# toplevel_os.net
KiCad netlist of a schematic drawn in Altium Designer
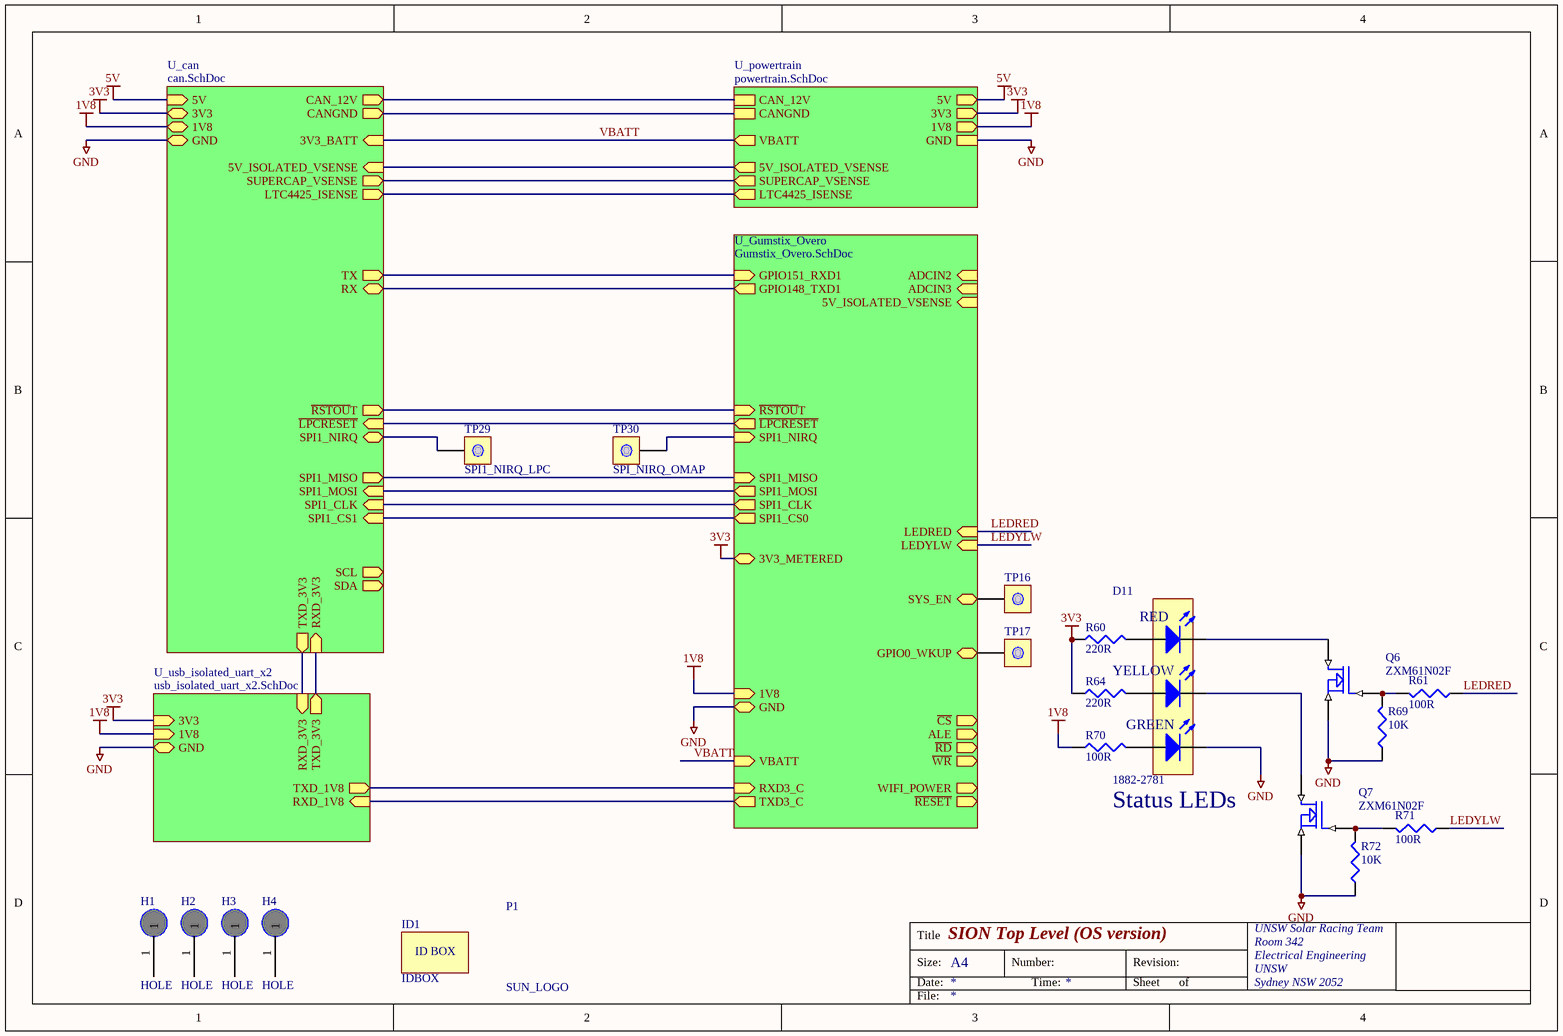
[diagram p0: toplevel_os.SchDoc]

(export (version "E")
  (design (tool "Eeschema 10.0.6"))
  (components
    (comp (ref "D11")
      (value "1882-2781")
      (footprint "LED_TRILEVEL")
      (description "Three level LED")
      (libsource (lib "RCLDQ") (part "LED-TRILEVEL"))
    )
    (comp (ref "H1")
      (value "HOLE")
      (footprint "Connectors:#6")
      (description "Hole")
      (libsource (lib "Miscellaneous") (part "HOLE"))
    )
    (comp (ref "H2")
      (value "HOLE")
      (footprint "Connectors:#6")
      (description "Hole")
      (libsource (lib "Miscellaneous") (part "HOLE"))
    )
    (comp (ref "H3")
      (value "HOLE")
      (footprint "Connectors:#6")
      (description "Hole")
      (libsource (lib "Miscellaneous") (part "HOLE"))
    )
    (comp (ref "H4")
      (value "HOLE")
      (footprint "Connectors:#6")
      (description "Hole")
      (libsource (lib "Miscellaneous") (part "HOLE"))
    )
    (comp (ref "ID1") (value "IDBOX") (footprint "IDBOX") (libsource (lib "Miscellaneous") (part "IDBOX")))
    (comp (ref "P1")
      (value "SUN_LOGO")
      (footprint "SUNSWIFTLOGO")
      (libsource (lib "Miscellaneous") (part "SUN_LOGO"))
    )
    (comp (ref "Q6")
      (value "ZXM61N02F")
      (footprint "SOT23-3")
      (description "1.7A, 20V N-Channel Enhancement mode FET")
      (libsource (lib "RCLDQ") (part "ZXM61N02F"))
    )
    (comp (ref "Q7")
      (value "ZXM61N02F")
      (footprint "SOT23-3")
      (description "1.7A, 20V N-Channel Enhancement mode FET")
      (libsource (lib "RCLDQ") (part "ZXM61N02F"))
    )
    (comp (ref "R60")
      (value "220R")
      (footprint "0603")
      (description "Resistor")
      (libsource (lib "RCLDQ") (part "RES1"))
    )
    (comp (ref "R61")
      (value "100R")
      (footprint "0603")
      (description "Resistor")
      (libsource (lib "RCLDQ") (part "RES1"))
    )
    (comp (ref "R64")
      (value "220R")
      (footprint "0603")
      (description "Resistor")
      (libsource (lib "RCLDQ") (part "RES1"))
    )
    (comp (ref "R69")
      (value "10K")
      (footprint "0603")
      (description "Resistor")
      (libsource (lib "RCLDQ") (part "RES1"))
    )
    (comp (ref "R70")
      (value "100R")
      (footprint "0603")
      (description "Resistor")
      (libsource (lib "RCLDQ") (part "RES1"))
    )
    (comp (ref "R71")
      (value "100R")
      (footprint "0603")
      (description "Resistor")
      (libsource (lib "RCLDQ") (part "RES1"))
    )
    (comp (ref "R72")
      (value "10K")
      (footprint "0603")
      (description "Resistor")
      (libsource (lib "RCLDQ") (part "RES1"))
    )
    (comp (ref "TP16")
      (value "SYS_EN")
      (footprint "TESTPOINT")
      (description "TEST POINT")
      (libsource (lib "") (part "TEST_1"))
    )
    (comp (ref "TP17")
      (value "WKUP")
      (footprint "TESTPOINT")
      (description "TEST POINT")
      (libsource (lib "") (part "TEST_1"))
    )
    (comp (ref "TP29")
      (value "SPI1_NIRQ_LPC")
      (footprint "TESTPOINT")
      (description "TEST POINT")
      (libsource (lib "") (part "TEST_1"))
    )
    (comp (ref "TP30")
      (value "SPI_NIRQ_OMAP")
      (footprint "TESTPOINT")
      (description "TEST POINT")
      (libsource (lib "Miscellaneous") (part "TEST"))
    )
  )
  (nets
    (net (code "8") (name "/GPIO0_WKUP") (class "Default")
      (node (ref "TP17") (pin "0") (pinfunction "TP_0") (pintype "passive"))
    )
    (net (code "10") (name "/LEDRED") (class "Default")
      (node (ref "R61") (pin "1") (pinfunction "1_1") (pintype "passive"))
    )
    (net (code "11") (name "/LEDYLW") (class "Default")
      (node (ref "R71") (pin "1") (pinfunction "1_1") (pintype "passive"))
    )
    (net (code "19") (name "/SPI1_NIRQ") (class "Default")
      (node (ref "TP30") (pin "0") (pinfunction "TP_0") (pintype "passive"))
    )
    (net (code "20") (name "/SPI1_NIRQ_1") (class "Default")
      (node (ref "TP29") (pin "0") (pinfunction "TP_0") (pintype "passive"))
    )
    (net (code "22") (name "/SYS_EN") (class "Default")
      (node (ref "TP16") (pin "0") (pinfunction "TP_0") (pintype "passive"))
    )
    (net (code "36") (name "1V8") (class "Default")
      (node (ref "R70") (pin "1") (pinfunction "1_1") (pintype "passive"))
    )
    (net (code "37") (name "3V3") (class "Default")
      (node (ref "R60") (pin "1") (pinfunction "1_1") (pintype "passive"))
      (node (ref "R64") (pin "1") (pinfunction "1_1") (pintype "passive"))
    )
    (net (code "39") (name "GND") (class "Default")
      (node (ref "D11") (pin "1") (pinfunction "K_1") (pintype "passive"))
      (node (ref "Q6") (pin "2") (pinfunction "S_2") (pintype "input"))
      (node (ref "Q7") (pin "2") (pinfunction "S_2") (pintype "input"))
      (node (ref "R69") (pin "1") (pinfunction "1_1") (pintype "passive"))
      (node (ref "R72") (pin "1") (pinfunction "1_1") (pintype "passive"))
    )
    (net (code "40") (name "Net-(D11-A-Pad4)") (class "Default")
      (node (ref "D11") (pin "4") (pinfunction "A_4") (pintype "passive"))
      (node (ref "R60") (pin "2") (pinfunction "2_2") (pintype "passive"))
    )
    (net (code "41") (name "Net-(D11-A-Pad5)") (class "Default")
      (node (ref "D11") (pin "5") (pinfunction "A_5") (pintype "passive"))
      (node (ref "R64") (pin "2") (pinfunction "2_2") (pintype "passive"))
    )
    (net (code "42") (name "Net-(D11-A-Pad6)") (class "Default")
      (node (ref "D11") (pin "6") (pinfunction "A_6") (pintype "passive"))
      (node (ref "R70") (pin "2") (pinfunction "2_2") (pintype "passive"))
    )
    (net (code "43") (name "Net-(Q6-D)") (class "Default")
      (node (ref "D11") (pin "3") (pinfunction "K_3") (pintype "passive"))
      (node (ref "Q6") (pin "3") (pinfunction "D_3") (pintype "input"))
    )
    (net (code "44") (name "Net-(Q6-G)") (class "Default")
      (node (ref "Q6") (pin "1") (pinfunction "G_1") (pintype "input"))
      (node (ref "R61") (pin "2") (pinfunction "2_2") (pintype "passive"))
      (node (ref "R69") (pin "2") (pinfunction "2_2") (pintype "passive"))
    )
    (net (code "45") (name "Net-(Q7-D)") (class "Default")
      (node (ref "D11") (pin "2") (pinfunction "K_2") (pintype "passive"))
      (node (ref "Q7") (pin "3") (pinfunction "D_3") (pintype "input"))
    )
    (net (code "46") (name "Net-(Q7-G)") (class "Default")
      (node (ref "Q7") (pin "1") (pinfunction "G_1") (pintype "input"))
      (node (ref "R71") (pin "2") (pinfunction "2_2") (pintype "passive"))
      (node (ref "R72") (pin "2") (pinfunction "2_2") (pintype "passive"))
    )
    (net (code "47") (name "unconnected-(H1-Pad1)") (class "Default")
      (node (ref "H1") (pin "1") (pinfunction "1_1") (pintype "passive"))
    )
    (net (code "48") (name "unconnected-(H2-Pad1)") (class "Default")
      (node (ref "H2") (pin "1") (pinfunction "1_1") (pintype "passive"))
    )
    (net (code "49") (name "unconnected-(H3-Pad1)") (class "Default")
      (node (ref "H3") (pin "1") (pinfunction "1_1") (pintype "passive"))
    )
    (net (code "50") (name "unconnected-(H4-Pad1)") (class "Default")
      (node (ref "H4") (pin "1") (pinfunction "1_1") (pintype "passive"))
    )
  )
)
